# usb-pd.net
KiCad netlist of a schematic drawn in EAGLE
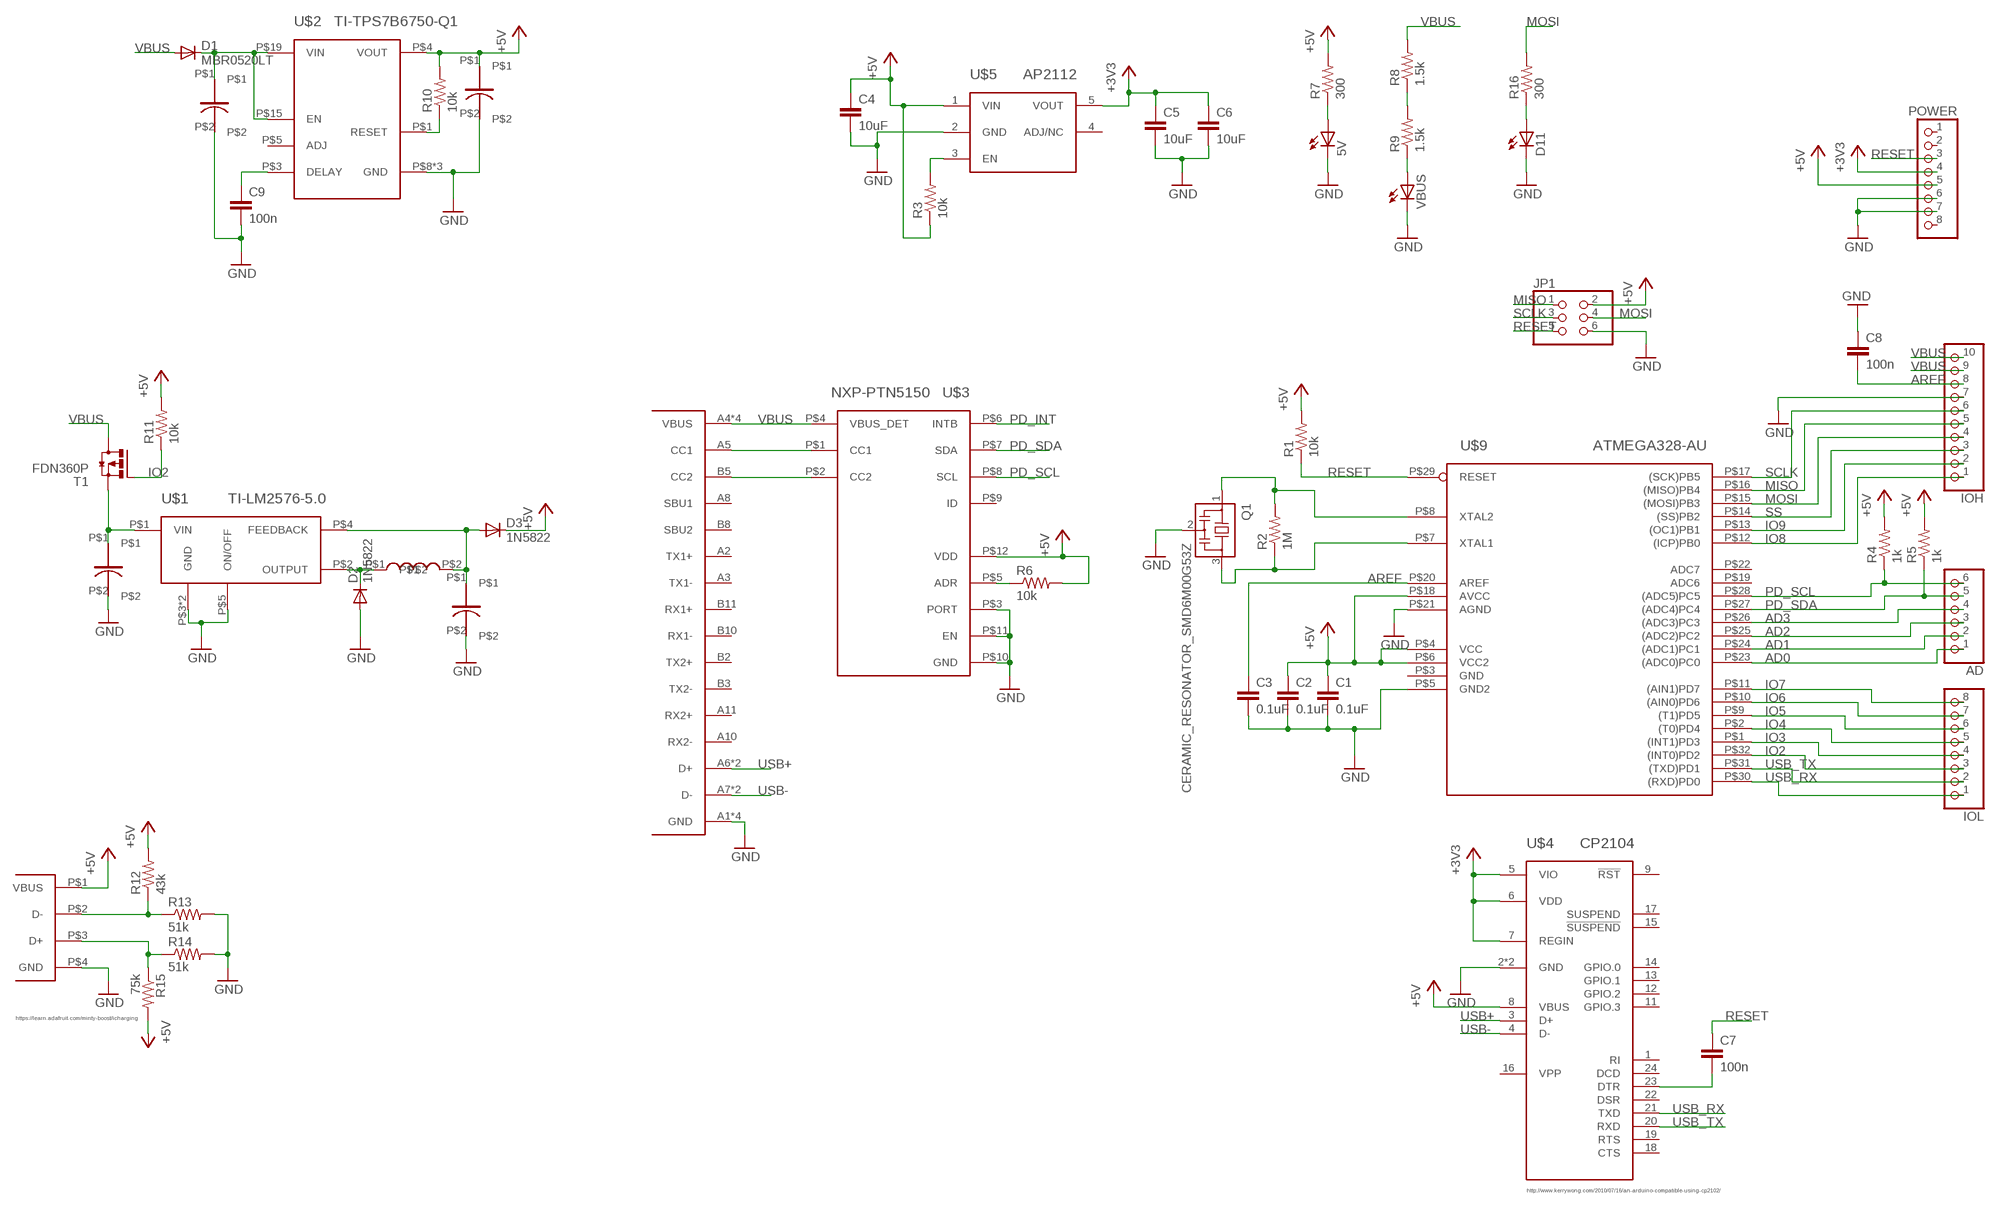
[diagram p0: schematic, sheet 1]

(export (version "E")
  (design (tool "Eeschema 10.0.6"))
  (components
    (comp (ref "5V")
      (value "LEDCHIPLED_0603")
      (footprint "eagle-import:CHIPLED_0603")
      (libsource (lib "eagle-import") (part "LEDCHIPLED_0603"))
    )
    (comp (ref "AD")
      (value "PINHD-1X6")
      (footprint "eagle-import:1X06")
      (libsource (lib "eagle-import") (part "PINHD-1X6"))
    )
    (comp (ref "C1")
      (value "0.1uF")
      (footprint "eagle-import:C0402")
      (libsource (lib "eagle-import") (part "C-EUC0402"))
    )
    (comp (ref "C2")
      (value "0.1uF")
      (footprint "eagle-import:C0402")
      (libsource (lib "eagle-import") (part "C-EUC0402"))
    )
    (comp (ref "C3")
      (value "0.1uF")
      (footprint "eagle-import:C0402")
      (libsource (lib "eagle-import") (part "C-EUC0402"))
    )
    (comp (ref "C4")
      (value "10uF")
      (footprint "eagle-import:C0805")
      (libsource (lib "eagle-import") (part "C-EUC0805"))
    )
    (comp (ref "C5")
      (value "10uF")
      (footprint "eagle-import:C0805")
      (libsource (lib "eagle-import") (part "C-EUC0805"))
    )
    (comp (ref "C6")
      (value "10uF")
      (footprint "eagle-import:C0805")
      (libsource (lib "eagle-import") (part "C-EUC0805"))
    )
    (comp (ref "C7")
      (value "100n")
      (footprint "eagle-import:C0402")
      (libsource (lib "eagle-import") (part "C-EUC0402"))
    )
    (comp (ref "C8")
      (value "100n")
      (footprint "eagle-import:C0402")
      (libsource (lib "eagle-import") (part "C-EUC0402"))
    )
    (comp (ref "C9")
      (value "100n")
      (footprint "eagle-import:C0603")
      (libsource (lib "eagle-import") (part "C-EUC0603"))
    )
    (comp (ref "C10")
      (value "UWT1V101MCL1GS")
      (footprint "eagle-import:UWT1V101MCL1GS")
      (libsource (lib "eagle-import") (part "UWT1V101MCL1GS"))
    )
    (comp (ref "C11")
      (value "AVE108M10G24T-F")
      (footprint "eagle-import:AVE108M10G")
      (libsource (lib "eagle-import") (part "AVE108M10G24T-F"))
    )
    (comp (ref "C12")
      (value "WURTH-865080543009-47uF")
      (footprint "eagle-import:WURTH-865090543005")
      (libsource (lib "eagle-import") (part "WURTH-865080543009"))
    )
    (comp (ref "C13")
      (value "WURTH-865090543005-22uF")
      (footprint "eagle-import:WURTH-865090543005")
      (libsource (lib "eagle-import") (part "WURTH-865090543005"))
    )
    (comp (ref "D1")
      (value "MBR0520LT")
      (footprint "eagle-import:SOD123")
      (libsource (lib "eagle-import") (part "MBR0520LT"))
    )
    (comp (ref "D2")
      (value "1N5822")
      (footprint "eagle-import:DO201-15")
      (libsource (lib "eagle-import") (part "1N5400"))
    )
    (comp (ref "D3")
      (value "1N5822")
      (footprint "eagle-import:DO201-15")
      (libsource (lib "eagle-import") (part "1N5400"))
    )
    (comp (ref "D11")
      (value "LEDCHIPLED_0603")
      (footprint "eagle-import:CHIPLED_0603")
      (libsource (lib "eagle-import") (part "LEDCHIPLED_0603"))
    )
    (comp (ref "IOH")
      (value "PINHD-1X10")
      (footprint "eagle-import:1X10")
      (libsource (lib "eagle-import") (part "PINHD-1X10"))
    )
    (comp (ref "IOL")
      (value "PINHD-1X8")
      (footprint "eagle-import:1X08")
      (libsource (lib "eagle-import") (part "PINHD-1X8"))
    )
    (comp (ref "J$1")
      (value "TYPE-C-12401548E4")
      (footprint "eagle-import:AMPHENOL-TYPE-C-12401548E4")
      (libsource (lib "eagle-import") (part "TYPE-C-12401548E4"))
    )
    (comp (ref "J$2")
      (value "UE27AC54100")
      (footprint "eagle-import:UE27AC54100")
      (libsource (lib "eagle-import") (part "UE27AC54100"))
    )
    (comp (ref "JP1")
      (value "PINHD-2X3")
      (footprint "eagle-import:2X03")
      (libsource (lib "eagle-import") (part "PINHD-2X3"))
    )
    (comp (ref "POWER")
      (value "PINHD-1X8")
      (footprint "eagle-import:1X08")
      (libsource (lib "eagle-import") (part "PINHD-1X8"))
    )
    (comp (ref "Q1")
      (value "CERAMIC_RESONATOR_SMD6M00G53Z")
      (footprint "eagle-import:CERAMIC_RESONATOR_SMD")
      (fields (field (name "MPN") "CSTCR6M00G53-R0"))
      (libsource (lib "eagle-import") (part "CERAMIC_RESONATOR_SMD6M00G53Z"))
    )
    (comp (ref "R1")
      (value "10k")
      (footprint "eagle-import:R0402")
      (libsource (lib "eagle-import") (part "R-US_R0402"))
    )
    (comp (ref "R2")
      (value "1M")
      (footprint "eagle-import:R0402")
      (libsource (lib "eagle-import") (part "R-US_R0402"))
    )
    (comp (ref "R3")
      (value "10k")
      (footprint "eagle-import:R0402")
      (libsource (lib "eagle-import") (part "R-US_R0402"))
    )
    (comp (ref "R4")
      (value "1k")
      (footprint "eagle-import:R0402")
      (libsource (lib "eagle-import") (part "R-US_R0402"))
    )
    (comp (ref "R5")
      (value "1k")
      (footprint "eagle-import:R0402")
      (libsource (lib "eagle-import") (part "R-US_R0402"))
    )
    (comp (ref "R6")
      (value "10k")
      (footprint "eagle-import:R0402")
      (libsource (lib "eagle-import") (part "R-US_R0402"))
    )
    (comp (ref "R7")
      (value "300")
      (footprint "eagle-import:R0402")
      (libsource (lib "eagle-import") (part "R-US_R0402"))
    )
    (comp (ref "R8")
      (value "1.5k")
      (footprint "eagle-import:R0402")
      (libsource (lib "eagle-import") (part "R-US_R0402"))
    )
    (comp (ref "R9")
      (value "1.5k")
      (footprint "eagle-import:R0402")
      (libsource (lib "eagle-import") (part "R-US_R0402"))
    )
    (comp (ref "R10")
      (value "10k")
      (footprint "eagle-import:R0805")
      (libsource (lib "eagle-import") (part "R-US_R0805"))
    )
    (comp (ref "R11")
      (value "10k")
      (footprint "eagle-import:R0402")
      (libsource (lib "eagle-import") (part "R-US_R0402"))
    )
    (comp (ref "R12")
      (value "43k")
      (footprint "eagle-import:R0402")
      (libsource (lib "eagle-import") (part "R-US_R0402"))
    )
    (comp (ref "R13")
      (value "51k")
      (footprint "eagle-import:R0402")
      (libsource (lib "eagle-import") (part "R-US_R0402"))
    )
    (comp (ref "R14")
      (value "51k")
      (footprint "eagle-import:R0402")
      (libsource (lib "eagle-import") (part "R-US_R0402"))
    )
    (comp (ref "R15")
      (value "75k")
      (footprint "eagle-import:R0402")
      (libsource (lib "eagle-import") (part "R-US_R0402"))
    )
    (comp (ref "R16")
      (value "300")
      (footprint "eagle-import:R0402")
      (libsource (lib "eagle-import") (part "R-US_R0402"))
    )
    (comp (ref "T1")
      (value "FDN360P")
      (footprint "eagle-import:SUPER-SOT3")
      (libsource (lib "eagle-import") (part "FDN360P"))
    )
    (comp (ref "U$1")
      (value "TI-LM2576-5.0")
      (footprint "eagle-import:TO-263")
      (libsource (lib "eagle-import") (part "TI-LM2576-5.0"))
    )
    (comp (ref "U$2")
      (value "TI-TPS7B6750-Q1")
      (footprint "eagle-import:HTSSOP-20")
      (libsource (lib "eagle-import") (part "TI-TPS7B6750-Q1"))
    )
    (comp (ref "U$3")
      (value "NXP-PTN5150")
      (footprint "eagle-import:X2QFN12")
      (libsource (lib "eagle-import") (part "NXP-PTN5150"))
    )
    (comp (ref "U$4")
      (value "CP2104")
      (footprint "eagle-import:QFN24_4X4")
      (libsource (lib "eagle-import") (part "CP2104"))
    )
    (comp (ref "U$5")
      (value "AP2112")
      (footprint "eagle-import:SOT23-5L")
      (libsource (lib "eagle-import") (part "AP2112"))
    )
    (comp (ref "U$7")
      (value "WEURTH-784771101")
      (footprint "eagle-import:1260")
      (libsource (lib "eagle-import") (part "WEURTH-784771101"))
    )
    (comp (ref "U$9")
      (value "ATMEGA328-AU")
      (footprint "eagle-import:32-TQFP")
      (libsource (lib "eagle-import") (part "ATMEGA328-AU"))
    )
    (comp (ref "VBUS")
      (value "LEDCHIPLED_0603")
      (footprint "eagle-import:CHIPLED_0603")
      (libsource (lib "eagle-import") (part "LEDCHIPLED_0603"))
    )
  )
  (nets
    (net (code "1") (name "+3V3") (class "Default")
      (node (ref "C5") (pin "1") (pinfunction "1_1") (pintype "passive"))
      (node (ref "C6") (pin "1") (pinfunction "1_1") (pintype "passive"))
      (node (ref "POWER") (pin "4") (pinfunction "4_4") (pintype "passive"))
      (node (ref "U$4") (pin "5") (pinfunction "VIO_5") (pintype "bidirectional"))
      (node (ref "U$4") (pin "6") (pinfunction "VDD_6") (pintype "bidirectional"))
      (node (ref "U$4") (pin "7") (pinfunction "REGIN_7") (pintype "bidirectional"))
      (node (ref "U$5") (pin "5") (pinfunction "VOUT_5") (pintype "bidirectional"))
    )
    (net (code "2") (name "+5V") (class "Default")
      (node (ref "C1") (pin "1") (pinfunction "1_1") (pintype "passive"))
      (node (ref "C13") (pin "P$1") (pinfunction "P$1_P$1") (pintype "bidirectional"))
      (node (ref "C2") (pin "1") (pinfunction "1_1") (pintype "passive"))
      (node (ref "C4") (pin "1") (pinfunction "1_1") (pintype "passive"))
      (node (ref "D3") (pin "C") (pinfunction "C_C") (pintype "passive"))
      (node (ref "J$2") (pin "P$1") (pinfunction "VBUS_P$1") (pintype "bidirectional"))
      (node (ref "JP1") (pin "2") (pinfunction "2_2") (pintype "passive"))
      (node (ref "POWER") (pin "5") (pinfunction "5_5") (pintype "passive"))
      (node (ref "R1") (pin "2") (pinfunction "2_2") (pintype "passive"))
      (node (ref "R10") (pin "2") (pinfunction "2_2") (pintype "passive"))
      (node (ref "R11") (pin "2") (pinfunction "2_2") (pintype "passive"))
      (node (ref "R12") (pin "2") (pinfunction "2_2") (pintype "passive"))
      (node (ref "R15") (pin "2") (pinfunction "2_2") (pintype "passive"))
      (node (ref "R3") (pin "1") (pinfunction "1_1") (pintype "passive"))
      (node (ref "R4") (pin "2") (pinfunction "2_2") (pintype "passive"))
      (node (ref "R5") (pin "2") (pinfunction "2_2") (pintype "passive"))
      (node (ref "R6") (pin "2") (pinfunction "2_2") (pintype "passive"))
      (node (ref "R7") (pin "2") (pinfunction "2_2") (pintype "passive"))
      (node (ref "U$2") (pin "P$4") (pinfunction "VOUT_P$4") (pintype "bidirectional"))
      (node (ref "U$3") (pin "P$12") (pinfunction "VDD_P$12") (pintype "bidirectional"))
      (node (ref "U$4") (pin "8") (pinfunction "VBUS_8") (pintype "bidirectional"))
      (node (ref "U$5") (pin "1") (pinfunction "VIN_1") (pintype "bidirectional"))
      (node (ref "U$9") (pin "P$18") (pinfunction "AVCC_P$18") (pintype "bidirectional"))
      (node (ref "U$9") (pin "P$4") (pinfunction "VCC_P$4") (pintype "bidirectional"))
      (node (ref "U$9") (pin "P$6") (pinfunction "VCC2_P$6") (pintype "bidirectional"))
    )
    (net (code "3") (name "/AD0") (class "Default")
      (node (ref "AD") (pin "1") (pinfunction "1_1") (pintype "passive"))
      (node (ref "U$9") (pin "P$23") (pinfunction "(ADC0)PC0_P$23") (pintype "bidirectional"))
    )
    (net (code "4") (name "/AD1") (class "Default")
      (node (ref "AD") (pin "2") (pinfunction "2_2") (pintype "passive"))
      (node (ref "U$9") (pin "P$24") (pinfunction "(ADC1)PC1_P$24") (pintype "bidirectional"))
    )
    (net (code "5") (name "/AD2") (class "Default")
      (node (ref "AD") (pin "3") (pinfunction "3_3") (pintype "passive"))
      (node (ref "U$9") (pin "P$25") (pinfunction "(ADC2)PC2_P$25") (pintype "bidirectional"))
    )
    (net (code "6") (name "/AD3") (class "Default")
      (node (ref "AD") (pin "4") (pinfunction "4_4") (pintype "passive"))
      (node (ref "U$9") (pin "P$26") (pinfunction "(ADC3)PC3_P$26") (pintype "bidirectional"))
    )
    (net (code "7") (name "/AREF") (class "Default")
      (node (ref "C3") (pin "1") (pinfunction "1_1") (pintype "passive"))
      (node (ref "C8") (pin "2") (pinfunction "2_2") (pintype "passive"))
      (node (ref "IOH") (pin "8") (pinfunction "8_8") (pintype "passive"))
      (node (ref "U$9") (pin "P$20") (pinfunction "AREF_P$20") (pintype "bidirectional"))
    )
    (net (code "8") (name "/IO2") (class "Default")
      (node (ref "IOL") (pin "3") (pinfunction "3_3") (pintype "passive"))
      (node (ref "R11") (pin "1") (pinfunction "1_1") (pintype "passive"))
      (node (ref "T1") (pin "1") (pinfunction "G_1") (pintype "passive"))
      (node (ref "U$9") (pin "P$32") (pinfunction "(INT0)PD2_P$32") (pintype "bidirectional"))
    )
    (net (code "9") (name "/IO3") (class "Default")
      (node (ref "IOL") (pin "4") (pinfunction "4_4") (pintype "passive"))
      (node (ref "U$9") (pin "P$1") (pinfunction "(INT1)PD3_P$1") (pintype "bidirectional"))
    )
    (net (code "10") (name "/IO4") (class "Default")
      (node (ref "IOL") (pin "5") (pinfunction "5_5") (pintype "passive"))
      (node (ref "U$9") (pin "P$2") (pinfunction "(T0)PD4_P$2") (pintype "bidirectional"))
    )
    (net (code "11") (name "/IO5") (class "Default")
      (node (ref "IOL") (pin "6") (pinfunction "6_6") (pintype "passive"))
      (node (ref "U$9") (pin "P$9") (pinfunction "(T1)PD5_P$9") (pintype "bidirectional"))
    )
    (net (code "12") (name "/IO6") (class "Default")
      (node (ref "IOL") (pin "7") (pinfunction "7_7") (pintype "passive"))
      (node (ref "U$9") (pin "P$10") (pinfunction "(AIN0)PD6_P$10") (pintype "bidirectional"))
    )
    (net (code "13") (name "/IO7") (class "Default")
      (node (ref "IOL") (pin "8") (pinfunction "8_8") (pintype "passive"))
      (node (ref "U$9") (pin "P$11") (pinfunction "(AIN1)PD7_P$11") (pintype "bidirectional"))
    )
    (net (code "14") (name "/IO8") (class "Default")
      (node (ref "IOH") (pin "1") (pinfunction "1_1") (pintype "passive"))
      (node (ref "U$9") (pin "P$12") (pinfunction "(ICP)PB0_P$12") (pintype "bidirectional"))
    )
    (net (code "15") (name "/IO9") (class "Default")
      (node (ref "IOH") (pin "2") (pinfunction "2_2") (pintype "passive"))
      (node (ref "U$9") (pin "P$13") (pinfunction "(OC1)PB1_P$13") (pintype "bidirectional"))
    )
    (net (code "16") (name "/MISO") (class "Default")
      (node (ref "IOH") (pin "5") (pinfunction "5_5") (pintype "passive"))
      (node (ref "JP1") (pin "1") (pinfunction "1_1") (pintype "passive"))
      (node (ref "U$9") (pin "P$16") (pinfunction "(MISO)PB4_P$16") (pintype "bidirectional"))
    )
    (net (code "17") (name "/MOSI") (class "Default")
      (node (ref "IOH") (pin "4") (pinfunction "4_4") (pintype "passive"))
      (node (ref "JP1") (pin "4") (pinfunction "4_4") (pintype "passive"))
      (node (ref "R16") (pin "2") (pinfunction "2_2") (pintype "passive"))
      (node (ref "U$9") (pin "P$15") (pinfunction "(MOSI)PB3_P$15") (pintype "bidirectional"))
    )
    (net (code "18") (name "/PD_INT") (class "Default")
      (node (ref "U$3") (pin "P$6") (pinfunction "INTB_P$6") (pintype "bidirectional"))
    )
    (net (code "19") (name "/PD_SCL") (class "Default")
      (node (ref "AD") (pin "6") (pinfunction "6_6") (pintype "passive"))
      (node (ref "R4") (pin "1") (pinfunction "1_1") (pintype "passive"))
      (node (ref "U$3") (pin "P$8") (pinfunction "SCL_P$8") (pintype "bidirectional"))
      (node (ref "U$9") (pin "P$28") (pinfunction "(ADC5)PC5_P$28") (pintype "bidirectional"))
    )
    (net (code "20") (name "/PD_SDA") (class "Default")
      (node (ref "AD") (pin "5") (pinfunction "5_5") (pintype "passive"))
      (node (ref "R5") (pin "1") (pinfunction "1_1") (pintype "passive"))
      (node (ref "U$3") (pin "P$7") (pinfunction "SDA_P$7") (pintype "bidirectional"))
      (node (ref "U$9") (pin "P$27") (pinfunction "(ADC4)PC4_P$27") (pintype "bidirectional"))
    )
    (net (code "21") (name "/RESET") (class "Default")
      (node (ref "C7") (pin "1") (pinfunction "1_1") (pintype "passive"))
      (node (ref "JP1") (pin "5") (pinfunction "5_5") (pintype "passive"))
      (node (ref "POWER") (pin "3") (pinfunction "3_3") (pintype "passive"))
      (node (ref "R1") (pin "1") (pinfunction "1_1") (pintype "passive"))
      (node (ref "U$9") (pin "P$29") (pinfunction "RESET_P$29") (pintype "bidirectional"))
    )
    (net (code "22") (name "/SCLK") (class "Default")
      (node (ref "IOH") (pin "6") (pinfunction "6_6") (pintype "passive"))
      (node (ref "JP1") (pin "3") (pinfunction "3_3") (pintype "passive"))
      (node (ref "U$9") (pin "P$17") (pinfunction "(SCK)PB5_P$17") (pintype "bidirectional"))
    )
    (net (code "23") (name "/SS") (class "Default")
      (node (ref "IOH") (pin "3") (pinfunction "3_3") (pintype "passive"))
      (node (ref "U$9") (pin "P$14") (pinfunction "(SS)PB2_P$14") (pintype "bidirectional"))
    )
    (net (code "24") (name "/USB+") (class "Default")
      (node (ref "J$1") (pin "A6") (pinfunction "D+_A6") (pintype "bidirectional"))
      (node (ref "J$1") (pin "B6") (pinfunction "D+_B6") (pintype "bidirectional"))
      (node (ref "U$4") (pin "3") (pinfunction "D+_3") (pintype "bidirectional"))
    )
    (net (code "25") (name "/USB-") (class "Default")
      (node (ref "J$1") (pin "A7") (pinfunction "D-_A7") (pintype "bidirectional"))
      (node (ref "J$1") (pin "B7") (pinfunction "D-_B7") (pintype "bidirectional"))
      (node (ref "U$4") (pin "4") (pinfunction "D-_4") (pintype "bidirectional"))
    )
    (net (code "26") (name "/USB_RX") (class "Default")
      (node (ref "IOL") (pin "1") (pinfunction "1_1") (pintype "passive"))
      (node (ref "U$4") (pin "21") (pinfunction "TXD_21") (pintype "bidirectional"))
      (node (ref "U$9") (pin "P$30") (pinfunction "(RXD)PD0_P$30") (pintype "bidirectional"))
    )
    (net (code "27") (name "/USB_TX") (class "Default")
      (node (ref "IOL") (pin "2") (pinfunction "2_2") (pintype "passive"))
      (node (ref "U$4") (pin "20") (pinfunction "RXD_20") (pintype "bidirectional"))
      (node (ref "U$9") (pin "P$31") (pinfunction "(TXD)PD1_P$31") (pintype "bidirectional"))
    )
    (net (code "28") (name "/VBUS") (class "Default")
      (node (ref "D1") (pin "A") (pinfunction "A_A") (pintype "passive"))
      (node (ref "IOH") (pin "10") (pinfunction "10_10") (pintype "passive"))
      (node (ref "IOH") (pin "9") (pinfunction "9_9") (pintype "passive"))
      (node (ref "J$1") (pin "A4") (pinfunction "VBUS_A4") (pintype "bidirectional"))
      (node (ref "J$1") (pin "A9") (pinfunction "VBUS_A9") (pintype "bidirectional"))
      (node (ref "J$1") (pin "B4") (pinfunction "VBUS_B4") (pintype "bidirectional"))
      (node (ref "J$1") (pin "B9") (pinfunction "VBUS_B9") (pintype "bidirectional"))
      (node (ref "R8") (pin "2") (pinfunction "2_2") (pintype "passive"))
      (node (ref "T1") (pin "3") (pinfunction "D_3") (pintype "passive"))
      (node (ref "U$3") (pin "P$4") (pinfunction "VBUS_DET_P$4") (pintype "bidirectional"))
    )
    (net (code "29") (name "GND") (class "Default")
      (node (ref "5V") (pin "C") (pinfunction "C_C") (pintype "passive"))
      (node (ref "C1") (pin "2") (pinfunction "2_2") (pintype "passive"))
      (node (ref "C10") (pin "P$2") (pinfunction "P$2_P$2") (pintype "bidirectional"))
      (node (ref "C11") (pin "P$2") (pinfunction "P$2_P$2") (pintype "bidirectional"))
      (node (ref "C12") (pin "P$2") (pinfunction "P$2_P$2") (pintype "bidirectional"))
      (node (ref "C13") (pin "P$2") (pinfunction "P$2_P$2") (pintype "bidirectional"))
      (node (ref "C2") (pin "2") (pinfunction "2_2") (pintype "passive"))
      (node (ref "C3") (pin "2") (pinfunction "2_2") (pintype "passive"))
      (node (ref "C4") (pin "2") (pinfunction "2_2") (pintype "passive"))
      (node (ref "C5") (pin "2") (pinfunction "2_2") (pintype "passive"))
      (node (ref "C6") (pin "2") (pinfunction "2_2") (pintype "passive"))
      (node (ref "C8") (pin "1") (pinfunction "1_1") (pintype "passive"))
      (node (ref "C9") (pin "2") (pinfunction "2_2") (pintype "passive"))
      (node (ref "D11") (pin "C") (pinfunction "C_C") (pintype "passive"))
      (node (ref "D2") (pin "A") (pinfunction "A_A") (pintype "passive"))
      (node (ref "IOH") (pin "7") (pinfunction "7_7") (pintype "passive"))
      (node (ref "J$1") (pin "A1") (pinfunction "GND_A1") (pintype "bidirectional"))
      (node (ref "J$1") (pin "A12") (pinfunction "GND_A12") (pintype "bidirectional"))
      (node (ref "J$1") (pin "B1") (pinfunction "GND_B1") (pintype "bidirectional"))
      (node (ref "J$1") (pin "B12") (pinfunction "GND_B12") (pintype "bidirectional"))
      (node (ref "J$2") (pin "P$4") (pinfunction "GND_P$4") (pintype "bidirectional"))
      (node (ref "JP1") (pin "6") (pinfunction "6_6") (pintype "passive"))
      (node (ref "POWER") (pin "6") (pinfunction "6_6") (pintype "passive"))
      (node (ref "POWER") (pin "7") (pinfunction "7_7") (pintype "passive"))
      (node (ref "Q1") (pin "2") (pinfunction "2_2") (pintype "passive"))
      (node (ref "R13") (pin "2") (pinfunction "2_2") (pintype "passive"))
      (node (ref "R14") (pin "2") (pinfunction "2_2") (pintype "passive"))
      (node (ref "U$1") (pin "P$3") (pinfunction "GND_P$3") (pintype "bidirectional"))
      (node (ref "U$1") (pin "P$5") (pinfunction "ON/OFF_P$5") (pintype "bidirectional"))
      (node (ref "U$1") (pin "P$6") (pinfunction "GND_P$6") (pintype "bidirectional"))
      (node (ref "U$2") (pin "P$13") (pinfunction "GND_P$13") (pintype "bidirectional"))
      (node (ref "U$2") (pin "P$21") (pinfunction "GND_P$21") (pintype "bidirectional"))
      (node (ref "U$2") (pin "P$8") (pinfunction "GND_P$8") (pintype "bidirectional"))
      (node (ref "U$3") (pin "P$10") (pinfunction "GND_P$10") (pintype "bidirectional"))
      (node (ref "U$3") (pin "P$11") (pinfunction "EN_P$11") (pintype "bidirectional"))
      (node (ref "U$3") (pin "P$3") (pinfunction "PORT_P$3") (pintype "bidirectional"))
      (node (ref "U$4") (pin "2") (pinfunction "GND_2") (pintype "bidirectional"))
      (node (ref "U$4") (pin "25") (pinfunction "GND_25") (pintype "bidirectional"))
      (node (ref "U$5") (pin "2") (pinfunction "GND_2") (pintype "bidirectional"))
      (node (ref "U$9") (pin "P$21") (pinfunction "AGND_P$21") (pintype "bidirectional"))
      (node (ref "U$9") (pin "P$5") (pinfunction "GND2_P$5") (pintype "bidirectional"))
      (node (ref "VBUS") (pin "C") (pinfunction "C_C") (pintype "passive"))
    )
    (net (code "30") (name "Net-(5V-PadA)") (class "Default")
      (node (ref "5V") (pin "A") (pinfunction "A_A") (pintype "passive"))
      (node (ref "R7") (pin "1") (pinfunction "1_1") (pintype "passive"))
    )
    (net (code "31") (name "Net-(D11-PadA)") (class "Default")
      (node (ref "D11") (pin "A") (pinfunction "A_A") (pintype "passive"))
      (node (ref "R16") (pin "1") (pinfunction "1_1") (pintype "passive"))
    )
    (net (code "32") (name "Net-(J$1-CC1)") (class "Default")
      (node (ref "J$1") (pin "A5") (pinfunction "CC1_A5") (pintype "bidirectional"))
      (node (ref "U$3") (pin "P$1") (pinfunction "CC1_P$1") (pintype "bidirectional"))
    )
    (net (code "33") (name "Net-(J$1-CC2)") (class "Default")
      (node (ref "J$1") (pin "B5") (pinfunction "CC2_B5") (pintype "bidirectional"))
      (node (ref "U$3") (pin "P$2") (pinfunction "CC2_P$2") (pintype "bidirectional"))
    )
    (net (code "34") (name "Net-(J$2-D+)") (class "Default")
      (node (ref "J$2") (pin "P$3") (pinfunction "D+_P$3") (pintype "bidirectional"))
      (node (ref "R14") (pin "1") (pinfunction "1_1") (pintype "passive"))
      (node (ref "R15") (pin "1") (pinfunction "1_1") (pintype "passive"))
    )
    (net (code "35") (name "Net-(J$2-D-)") (class "Default")
      (node (ref "J$2") (pin "P$2") (pinfunction "D-_P$2") (pintype "bidirectional"))
      (node (ref "R12") (pin "1") (pinfunction "1_1") (pintype "passive"))
      (node (ref "R13") (pin "1") (pinfunction "1_1") (pintype "passive"))
    )
    (net (code "36") (name "Net-(R8-Pad1)") (class "Default")
      (node (ref "R8") (pin "1") (pinfunction "1_1") (pintype "passive"))
      (node (ref "R9") (pin "2") (pinfunction "2_2") (pintype "passive"))
    )
    (net (code "37") (name "Net-(R9-Pad1)") (class "Default")
      (node (ref "R9") (pin "1") (pinfunction "1_1") (pintype "passive"))
      (node (ref "VBUS") (pin "A") (pinfunction "A_A") (pintype "passive"))
    )
    (net (code "38") (name "Net-(T1-S)") (class "Default")
      (node (ref "C10") (pin "P$1") (pinfunction "P$1_P$1") (pintype "bidirectional"))
      (node (ref "T1") (pin "2") (pinfunction "S_2") (pintype "passive"))
      (node (ref "U$1") (pin "P$1") (pinfunction "VIN_P$1") (pintype "bidirectional"))
    )
    (net (code "39") (name "Net-(U$1-FEEDBACK)") (class "Default")
      (node (ref "C11") (pin "P$1") (pinfunction "P$1_P$1") (pintype "bidirectional"))
      (node (ref "D3") (pin "A") (pinfunction "A_A") (pintype "passive"))
      (node (ref "U$1") (pin "P$4") (pinfunction "FEEDBACK_P$4") (pintype "bidirectional"))
      (node (ref "U$7") (pin "P$2") (pinfunction "P$2_P$2") (pintype "bidirectional"))
    )
    (net (code "40") (name "Net-(U$1-OUTPUT)") (class "Default")
      (node (ref "D2") (pin "C") (pinfunction "C_C") (pintype "passive"))
      (node (ref "U$1") (pin "P$2") (pinfunction "OUTPUT_P$2") (pintype "bidirectional"))
      (node (ref "U$7") (pin "P$1") (pinfunction "P$1_P$1") (pintype "bidirectional"))
    )
    (net (code "41") (name "Net-(U$2-DELAY)") (class "Default")
      (node (ref "C9") (pin "1") (pinfunction "1_1") (pintype "passive"))
      (node (ref "U$2") (pin "P$3") (pinfunction "DELAY_P$3") (pintype "bidirectional"))
    )
    (net (code "42") (name "Net-(U$2-EN)") (class "Default")
      (node (ref "C12") (pin "P$1") (pinfunction "P$1_P$1") (pintype "bidirectional"))
      (node (ref "D1") (pin "C") (pinfunction "C_C") (pintype "passive"))
      (node (ref "U$2") (pin "P$15") (pinfunction "EN_P$15") (pintype "bidirectional"))
      (node (ref "U$2") (pin "P$19") (pinfunction "VIN_P$19") (pintype "bidirectional"))
    )
    (net (code "43") (name "Net-(U$2-RESET)") (class "Default")
      (node (ref "R10") (pin "1") (pinfunction "1_1") (pintype "passive"))
      (node (ref "U$2") (pin "P$1") (pinfunction "RESET_P$1") (pintype "bidirectional"))
    )
    (net (code "44") (name "Net-(U$3-ADR)") (class "Default")
      (node (ref "R6") (pin "1") (pinfunction "1_1") (pintype "passive"))
      (node (ref "U$3") (pin "P$5") (pinfunction "ADR_P$5") (pintype "bidirectional"))
    )
    (net (code "45") (name "Net-(U$4-DTR)") (class "Default")
      (node (ref "C7") (pin "2") (pinfunction "2_2") (pintype "passive"))
      (node (ref "U$4") (pin "23") (pinfunction "DTR_23") (pintype "bidirectional"))
    )
    (net (code "46") (name "Net-(U$5-EN)") (class "Default")
      (node (ref "R3") (pin "2") (pinfunction "2_2") (pintype "passive"))
      (node (ref "U$5") (pin "3") (pinfunction "EN_3") (pintype "bidirectional"))
    )
    (net (code "47") (name "Net-(U$9-XTAL1)") (class "Default")
      (node (ref "Q1") (pin "3") (pinfunction "3_3") (pintype "passive"))
      (node (ref "R2") (pin "1") (pinfunction "1_1") (pintype "passive"))
      (node (ref "U$9") (pin "P$7") (pinfunction "XTAL1_P$7") (pintype "bidirectional"))
    )
    (net (code "48") (name "Net-(U$9-XTAL2)") (class "Default")
      (node (ref "Q1") (pin "1") (pinfunction "1_1") (pintype "passive"))
      (node (ref "R2") (pin "2") (pinfunction "2_2") (pintype "passive"))
      (node (ref "U$9") (pin "P$8") (pinfunction "XTAL2_P$8") (pintype "bidirectional"))
    )
    (net (code "49") (name "unconnected-(J$1-RX1+-PadB11)") (class "Default")
      (node (ref "J$1") (pin "B11") (pinfunction "RX1+_B11") (pintype "bidirectional"))
    )
    (net (code "50") (name "unconnected-(J$1-RX1--PadB10)") (class "Default")
      (node (ref "J$1") (pin "B10") (pinfunction "RX1-_B10") (pintype "bidirectional"))
    )
    (net (code "51") (name "unconnected-(J$1-RX2+-PadA11)") (class "Default")
      (node (ref "J$1") (pin "A11") (pinfunction "RX2+_A11") (pintype "bidirectional"))
    )
    (net (code "52") (name "unconnected-(J$1-RX2--PadA10)") (class "Default")
      (node (ref "J$1") (pin "A10") (pinfunction "RX2-_A10") (pintype "bidirectional"))
    )
    (net (code "53") (name "unconnected-(J$1-SBU1-PadA8)") (class "Default")
      (node (ref "J$1") (pin "A8") (pinfunction "SBU1_A8") (pintype "bidirectional"))
    )
    (net (code "54") (name "unconnected-(J$1-SBU2-PadB8)") (class "Default")
      (node (ref "J$1") (pin "B8") (pinfunction "SBU2_B8") (pintype "bidirectional"))
    )
    (net (code "55") (name "unconnected-(J$1-TX1+-PadA2)") (class "Default")
      (node (ref "J$1") (pin "A2") (pinfunction "TX1+_A2") (pintype "bidirectional"))
    )
    (net (code "56") (name "unconnected-(J$1-TX1--PadA3)") (class "Default")
      (node (ref "J$1") (pin "A3") (pinfunction "TX1-_A3") (pintype "bidirectional"))
    )
    (net (code "57") (name "unconnected-(J$1-TX2+-PadB2)") (class "Default")
      (node (ref "J$1") (pin "B2") (pinfunction "TX2+_B2") (pintype "bidirectional"))
    )
    (net (code "58") (name "unconnected-(J$1-TX2--PadB3)") (class "Default")
      (node (ref "J$1") (pin "B3") (pinfunction "TX2-_B3") (pintype "bidirectional"))
    )
    (net (code "59") (name "unconnected-(POWER-Pad1)") (class "Default")
      (node (ref "POWER") (pin "1") (pinfunction "1_1") (pintype "passive"))
    )
    (net (code "60") (name "unconnected-(POWER-Pad2)") (class "Default")
      (node (ref "POWER") (pin "2") (pinfunction "2_2") (pintype "passive"))
    )
    (net (code "61") (name "unconnected-(POWER-Pad8)") (class "Default")
      (node (ref "POWER") (pin "8") (pinfunction "8_8") (pintype "passive"))
    )
    (net (code "62") (name "unconnected-(U$2-ADJ-PadP$5)") (class "Default")
      (node (ref "U$2") (pin "P$5") (pinfunction "ADJ_P$5") (pintype "bidirectional"))
    )
    (net (code "63") (name "unconnected-(U$3-ID-PadP$9)") (class "Default")
      (node (ref "U$3") (pin "P$9") (pinfunction "ID_P$9") (pintype "bidirectional"))
    )
    (net (code "64") (name "unconnected-(U$4-CTS-Pad18)") (class "Default")
      (node (ref "U$4") (pin "18") (pinfunction "CTS_18") (pintype "bidirectional"))
    )
    (net (code "65") (name "unconnected-(U$4-DCD-Pad24)") (class "Default")
      (node (ref "U$4") (pin "24") (pinfunction "DCD_24") (pintype "bidirectional"))
    )
    (net (code "66") (name "unconnected-(U$4-DSR-Pad22)") (class "Default")
      (node (ref "U$4") (pin "22") (pinfunction "DSR_22") (pintype "bidirectional"))
    )
    (net (code "67") (name "unconnected-(U$4-GPIO.0-Pad14)") (class "Default")
      (node (ref "U$4") (pin "14") (pinfunction "GPIO.0_14") (pintype "bidirectional"))
    )
    (net (code "68") (name "unconnected-(U$4-GPIO.1-Pad13)") (class "Default")
      (node (ref "U$4") (pin "13") (pinfunction "GPIO.1_13") (pintype "bidirectional"))
    )
    (net (code "69") (name "unconnected-(U$4-GPIO.2-Pad12)") (class "Default")
      (node (ref "U$4") (pin "12") (pinfunction "GPIO.2_12") (pintype "bidirectional"))
    )
    (net (code "70") (name "unconnected-(U$4-GPIO.3-Pad11)") (class "Default")
      (node (ref "U$4") (pin "11") (pinfunction "GPIO.3_11") (pintype "bidirectional"))
    )
    (net (code "71") (name "unconnected-(U$4-RI-Pad1)") (class "Default")
      (node (ref "U$4") (pin "1") (pinfunction "RI_1") (pintype "bidirectional"))
    )
    (net (code "72") (name "unconnected-(U$4-RTS-Pad19)") (class "Default")
      (node (ref "U$4") (pin "19") (pinfunction "RTS_19") (pintype "bidirectional"))
    )
    (net (code "73") (name "unconnected-(U$4-SUSPEND-Pad17)") (class "Default")
      (node (ref "U$4") (pin "17") (pinfunction "SUSPEND_17") (pintype "bidirectional"))
    )
    (net (code "74") (name "unconnected-(U$4-VPP-Pad16)") (class "Default")
      (node (ref "U$4") (pin "16") (pinfunction "VPP_16") (pintype "input"))
    )
    (net (code "75") (name "unconnected-(U$4-~{RST}-Pad9)") (class "Default")
      (node (ref "U$4") (pin "9") (pinfunction "~{RST}_9") (pintype "bidirectional"))
    )
    (net (code "76") (name "unconnected-(U$4-~{SUSPEND}-Pad15)") (class "Default")
      (node (ref "U$4") (pin "15") (pinfunction "~{SUSPEND}_15") (pintype "bidirectional"))
    )
    (net (code "77") (name "unconnected-(U$5-ADJ{slash}NC-Pad4)") (class "Default")
      (node (ref "U$5") (pin "4") (pinfunction "ADJ/NC_4") (pintype "bidirectional"))
    )
    (net (code "78") (name "unconnected-(U$9-ADC6-PadP$19)") (class "Default")
      (node (ref "U$9") (pin "P$19") (pinfunction "ADC6_P$19") (pintype "bidirectional"))
    )
    (net (code "79") (name "unconnected-(U$9-ADC7-PadP$22)") (class "Default")
      (node (ref "U$9") (pin "P$22") (pinfunction "ADC7_P$22") (pintype "bidirectional"))
    )
    (net (code "80") (name "unconnected-(U$9-GND-PadP$3)") (class "Default")
      (node (ref "U$9") (pin "P$3") (pinfunction "GND_P$3") (pintype "bidirectional"))
    )
  )
)
